# SCHEMAT.net
KiCad netlist of a schematic drawn in EAGLE
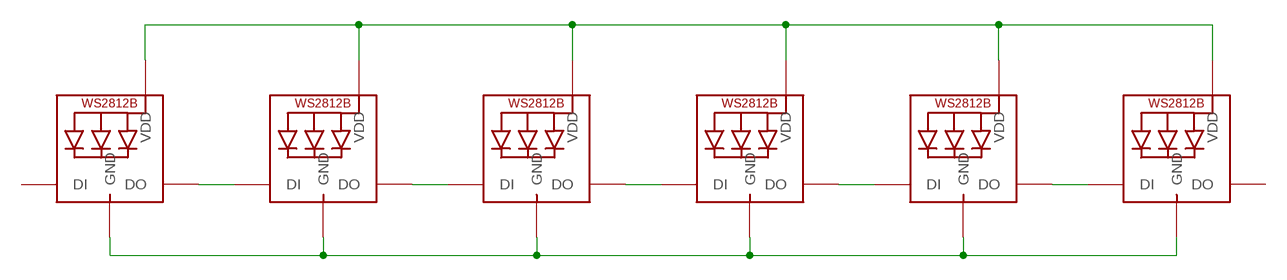
[diagram p0: schematic, sheet 1]

(export (version "E")
  (design (tool "Eeschema 10.0.6"))
  (components
    (comp (ref "LED1")
      (value "WS2812B5050")
      (footprint "eagle-import:WS2812B")
      (libsource (lib "eagle-import") (part "WS2812B5050"))
    )
    (comp (ref "LED2")
      (value "WS2812B5050")
      (footprint "eagle-import:WS2812B")
      (libsource (lib "eagle-import") (part "WS2812B5050"))
    )
    (comp (ref "LED3")
      (value "WS2812B5050")
      (footprint "eagle-import:WS2812B")
      (libsource (lib "eagle-import") (part "WS2812B5050"))
    )
    (comp (ref "LED4")
      (value "WS2812B5050")
      (footprint "eagle-import:WS2812B")
      (libsource (lib "eagle-import") (part "WS2812B5050"))
    )
    (comp (ref "LED5")
      (value "WS2812B5050")
      (footprint "eagle-import:WS2812B")
      (libsource (lib "eagle-import") (part "WS2812B5050"))
    )
    (comp (ref "LED6")
      (value "WS2812B5050")
      (footprint "eagle-import:WS2812B")
      (libsource (lib "eagle-import") (part "WS2812B5050"))
    )
  )
  (nets
    (net (code "1") (name "Net-(LED1-DO)") (class "Default")
      (node (ref "LED1") (pin "2-DOUT") (pinfunction "DO_2-DOUT") (pintype "output"))
      (node (ref "LED2") (pin "4-DIN") (pinfunction "DI_4-DIN") (pintype "input"))
    )
    (net (code "2") (name "Net-(LED1-GND)") (class "Default")
      (node (ref "LED1") (pin "3-GND") (pinfunction "GND_3-GND") (pintype "power_in"))
      (node (ref "LED2") (pin "3-GND") (pinfunction "GND_3-GND") (pintype "power_in"))
      (node (ref "LED3") (pin "3-GND") (pinfunction "GND_3-GND") (pintype "power_in"))
      (node (ref "LED4") (pin "3-GND") (pinfunction "GND_3-GND") (pintype "power_in"))
      (node (ref "LED5") (pin "3-GND") (pinfunction "GND_3-GND") (pintype "power_in"))
      (node (ref "LED6") (pin "3-GND") (pinfunction "GND_3-GND") (pintype "power_in"))
    )
    (net (code "3") (name "Net-(LED1-VDD)") (class "Default")
      (node (ref "LED1") (pin "1-VDD") (pinfunction "VDD_1-VDD") (pintype "power_in"))
      (node (ref "LED2") (pin "1-VDD") (pinfunction "VDD_1-VDD") (pintype "power_in"))
      (node (ref "LED3") (pin "1-VDD") (pinfunction "VDD_1-VDD") (pintype "power_in"))
      (node (ref "LED4") (pin "1-VDD") (pinfunction "VDD_1-VDD") (pintype "power_in"))
      (node (ref "LED5") (pin "1-VDD") (pinfunction "VDD_1-VDD") (pintype "power_in"))
      (node (ref "LED6") (pin "1-VDD") (pinfunction "VDD_1-VDD") (pintype "power_in"))
    )
    (net (code "4") (name "Net-(LED2-DO)") (class "Default")
      (node (ref "LED2") (pin "2-DOUT") (pinfunction "DO_2-DOUT") (pintype "output"))
      (node (ref "LED3") (pin "4-DIN") (pinfunction "DI_4-DIN") (pintype "input"))
    )
    (net (code "5") (name "Net-(LED3-DO)") (class "Default")
      (node (ref "LED3") (pin "2-DOUT") (pinfunction "DO_2-DOUT") (pintype "output"))
      (node (ref "LED4") (pin "4-DIN") (pinfunction "DI_4-DIN") (pintype "input"))
    )
    (net (code "6") (name "Net-(LED4-DO)") (class "Default")
      (node (ref "LED4") (pin "2-DOUT") (pinfunction "DO_2-DOUT") (pintype "output"))
      (node (ref "LED5") (pin "4-DIN") (pinfunction "DI_4-DIN") (pintype "input"))
    )
    (net (code "7") (name "Net-(LED5-DO)") (class "Default")
      (node (ref "LED5") (pin "2-DOUT") (pinfunction "DO_2-DOUT") (pintype "output"))
      (node (ref "LED6") (pin "4-DIN") (pinfunction "DI_4-DIN") (pintype "input"))
    )
    (net (code "8") (name "unconnected-(LED1-DI-Pad4-DIN)") (class "Default")
      (node (ref "LED1") (pin "4-DIN") (pinfunction "DI_4-DIN") (pintype "input"))
    )
    (net (code "9") (name "unconnected-(LED6-DO-Pad2-DOUT)") (class "Default")
      (node (ref "LED6") (pin "2-DOUT") (pinfunction "DO_2-DOUT") (pintype "output"))
    )
  )
)
